# LQFP48_TO_DIP.net
KiCad netlist of a schematic drawn in EasyEDA
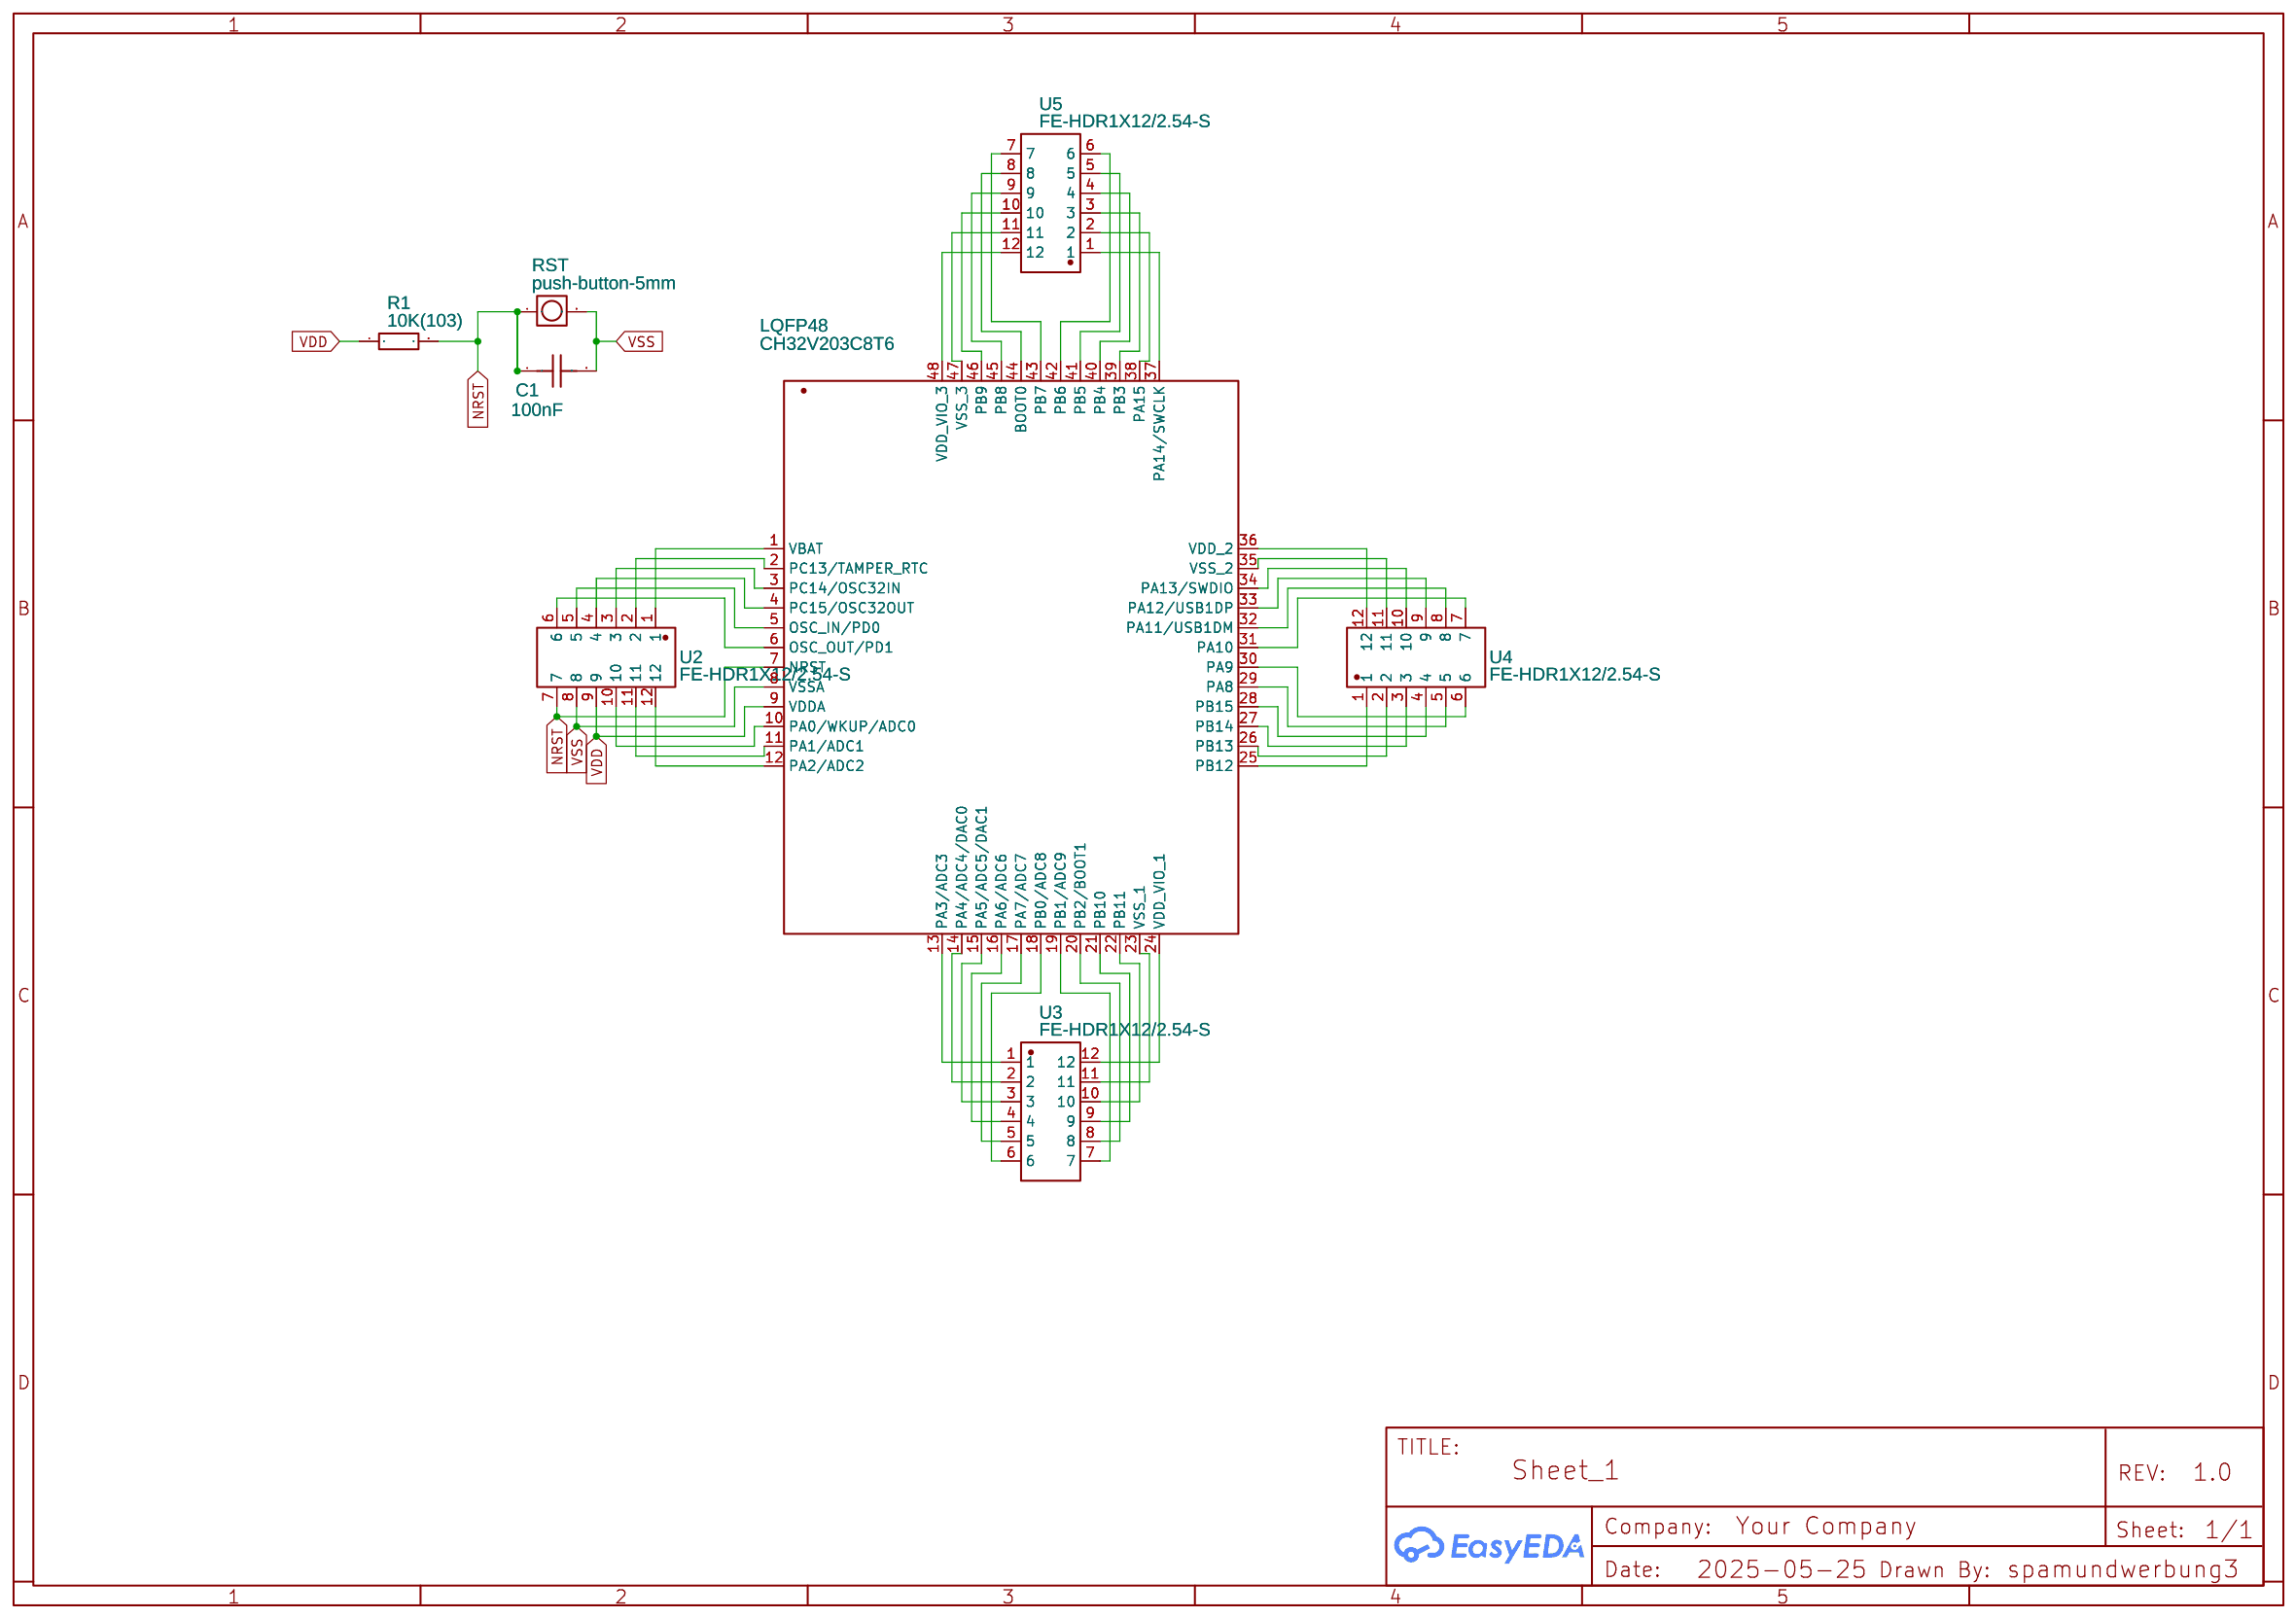
[diagram p0: schematic sheet]

(export (version "E")
  (design (tool "Eeschema 10.0.6"))
  (components
    (comp (ref "C1")
      (value "100nF")
      (fields (field (name "Manufacturer Part") "C0603B104K500NT") (field (name "Manufacturer") "TORCH(火炬)"))
      (libsource (lib "") (part "C100NF_0603"))
    )
    (comp (ref "LQFP48")
      (value "CH32V203C8T6")
      (fields (field (name "Manufacturer") "WCH(南京沁恒)"))
      (libsource (lib "") (part "CH32V203C8T6"))
    )
    (comp (ref "R1")
      (value "10K(103)")
      (fields (field (name "Manufacturer Part") "RC0603JR-0710KL") (field (name "Manufacturer") "YAGEO"))
      (libsource (lib "") (part "0603 10K RESISTOR (SMD)"))
    )
    (comp (ref "RST") (value "push-button-5mm") (libsource (lib "") (part "push-button-5mm")))
    (comp (ref "U2")
      (value "FE-HDR1X12/2.54-S")
      (fields (field (name "Manufacturer Part") "Fe-HDR1X12/2.54-S"))
      (libsource (lib "") (part "FE-HDR1X12/2.54-S_3"))
    )
    (comp (ref "U3")
      (value "FE-HDR1X12/2.54-S")
      (fields (field (name "Manufacturer Part") "Fe-HDR1X12/2.54-S"))
      (libsource (lib "") (part "FE-HDR1X12/2.54-S_2"))
    )
    (comp (ref "U4")
      (value "FE-HDR1X12/2.54-S")
      (fields (field (name "Manufacturer Part") "Fe-HDR1X12/2.54-S"))
      (libsource (lib "") (part "FE-HDR1X12/2.54-S"))
    )
    (comp (ref "U5")
      (value "FE-HDR1X12/2.54-S")
      (fields (field (name "Manufacturer Part") "Fe-HDR1X12/2.54-S"))
      (libsource (lib "") (part "FE-HDR1X12/2.54-S_1"))
    )
  )
  (nets
    (net (code "1") (name "NRST") (class "Default")
      (node (ref "C1") (pin "1") (pinfunction "1_1") (pintype "unspecified"))
      (node (ref "LQFP48") (pin "7") (pinfunction "NRST_7") (pintype "unspecified"))
      (node (ref "R1") (pin "2") (pinfunction "2_2") (pintype "input"))
      (node (ref "RST") (pin "1") (pinfunction "1_1") (pintype "unspecified"))
      (node (ref "U2") (pin "7") (pinfunction "7_7") (pintype "unspecified"))
    )
    (net (code "2") (name "Net-(LQFP48-BOOT0)") (class "Default")
      (node (ref "LQFP48") (pin "44") (pinfunction "BOOT0_44") (pintype "unspecified"))
      (node (ref "U5") (pin "8") (pinfunction "8_8") (pintype "unspecified"))
    )
    (net (code "3") (name "Net-(LQFP48-OSC_IN{slash}PD0)") (class "Default")
      (node (ref "LQFP48") (pin "5") (pinfunction "OSC_IN/PD0_5") (pintype "unspecified"))
      (node (ref "U2") (pin "5") (pinfunction "5_5") (pintype "unspecified"))
    )
    (net (code "4") (name "Net-(LQFP48-OSC_OUT{slash}PD1)") (class "Default")
      (node (ref "LQFP48") (pin "6") (pinfunction "OSC_OUT/PD1_6") (pintype "unspecified"))
      (node (ref "U2") (pin "6") (pinfunction "6_6") (pintype "unspecified"))
    )
    (net (code "5") (name "Net-(LQFP48-PA0{slash}WKUP{slash}ADC0)") (class "Default")
      (node (ref "LQFP48") (pin "10") (pinfunction "PA0/WKUP/ADC0_10") (pintype "unspecified"))
      (node (ref "U2") (pin "10") (pinfunction "10_10") (pintype "unspecified"))
    )
    (net (code "6") (name "Net-(LQFP48-PA1{slash}ADC1)") (class "Default")
      (node (ref "LQFP48") (pin "11") (pinfunction "PA1/ADC1_11") (pintype "unspecified"))
      (node (ref "U2") (pin "11") (pinfunction "11_11") (pintype "unspecified"))
    )
    (net (code "7") (name "Net-(LQFP48-PA2{slash}ADC2)") (class "Default")
      (node (ref "LQFP48") (pin "12") (pinfunction "PA2/ADC2_12") (pintype "unspecified"))
      (node (ref "U2") (pin "12") (pinfunction "12_12") (pintype "unspecified"))
    )
    (net (code "8") (name "Net-(LQFP48-PA3{slash}ADC3)") (class "Default")
      (node (ref "LQFP48") (pin "13") (pinfunction "PA3/ADC3_13") (pintype "unspecified"))
      (node (ref "U3") (pin "1") (pinfunction "1_1") (pintype "unspecified"))
    )
    (net (code "9") (name "Net-(LQFP48-PA4{slash}ADC4{slash}DAC0)") (class "Default")
      (node (ref "LQFP48") (pin "14") (pinfunction "PA4/ADC4/DAC0_14") (pintype "unspecified"))
      (node (ref "U3") (pin "2") (pinfunction "2_2") (pintype "unspecified"))
    )
    (net (code "10") (name "Net-(LQFP48-PA5{slash}ADC5{slash}DAC1)") (class "Default")
      (node (ref "LQFP48") (pin "15") (pinfunction "PA5/ADC5/DAC1_15") (pintype "unspecified"))
      (node (ref "U3") (pin "3") (pinfunction "3_3") (pintype "unspecified"))
    )
    (net (code "11") (name "Net-(LQFP48-PA6{slash}ADC6)") (class "Default")
      (node (ref "LQFP48") (pin "16") (pinfunction "PA6/ADC6_16") (pintype "unspecified"))
      (node (ref "U3") (pin "4") (pinfunction "4_4") (pintype "unspecified"))
    )
    (net (code "12") (name "Net-(LQFP48-PA7{slash}ADC7)") (class "Default")
      (node (ref "LQFP48") (pin "17") (pinfunction "PA7/ADC7_17") (pintype "unspecified"))
      (node (ref "U3") (pin "5") (pinfunction "5_5") (pintype "unspecified"))
    )
    (net (code "13") (name "Net-(LQFP48-PA8)") (class "Default")
      (node (ref "LQFP48") (pin "29") (pinfunction "PA8_29") (pintype "unspecified"))
      (node (ref "U4") (pin "5") (pinfunction "5_5") (pintype "unspecified"))
    )
    (net (code "14") (name "Net-(LQFP48-PA9)") (class "Default")
      (node (ref "LQFP48") (pin "30") (pinfunction "PA9_30") (pintype "unspecified"))
      (node (ref "U4") (pin "6") (pinfunction "6_6") (pintype "unspecified"))
    )
    (net (code "15") (name "Net-(LQFP48-PA10)") (class "Default")
      (node (ref "LQFP48") (pin "31") (pinfunction "PA10_31") (pintype "unspecified"))
      (node (ref "U4") (pin "7") (pinfunction "7_7") (pintype "unspecified"))
    )
    (net (code "16") (name "Net-(LQFP48-PA11{slash}USB1DM)") (class "Default")
      (node (ref "LQFP48") (pin "32") (pinfunction "PA11/USB1DM_32") (pintype "unspecified"))
      (node (ref "U4") (pin "8") (pinfunction "8_8") (pintype "unspecified"))
    )
    (net (code "17") (name "Net-(LQFP48-PA12{slash}USB1DP)") (class "Default")
      (node (ref "LQFP48") (pin "33") (pinfunction "PA12/USB1DP_33") (pintype "unspecified"))
      (node (ref "U4") (pin "9") (pinfunction "9_9") (pintype "unspecified"))
    )
    (net (code "18") (name "Net-(LQFP48-PA13{slash}SWDIO)") (class "Default")
      (node (ref "LQFP48") (pin "34") (pinfunction "PA13/SWDIO_34") (pintype "unspecified"))
      (node (ref "U4") (pin "10") (pinfunction "10_10") (pintype "unspecified"))
    )
    (net (code "19") (name "Net-(LQFP48-PA14{slash}SWCLK)") (class "Default")
      (node (ref "LQFP48") (pin "37") (pinfunction "PA14/SWCLK_37") (pintype "unspecified"))
      (node (ref "U5") (pin "1") (pinfunction "1_1") (pintype "unspecified"))
    )
    (net (code "20") (name "Net-(LQFP48-PA15)") (class "Default")
      (node (ref "LQFP48") (pin "38") (pinfunction "PA15_38") (pintype "unspecified"))
      (node (ref "U5") (pin "2") (pinfunction "2_2") (pintype "unspecified"))
    )
    (net (code "21") (name "Net-(LQFP48-PB0{slash}ADC8)") (class "Default")
      (node (ref "LQFP48") (pin "18") (pinfunction "PB0/ADC8_18") (pintype "unspecified"))
      (node (ref "U3") (pin "6") (pinfunction "6_6") (pintype "unspecified"))
    )
    (net (code "22") (name "Net-(LQFP48-PB1{slash}ADC9)") (class "Default")
      (node (ref "LQFP48") (pin "19") (pinfunction "PB1/ADC9_19") (pintype "unspecified"))
      (node (ref "U3") (pin "7") (pinfunction "7_7") (pintype "unspecified"))
    )
    (net (code "23") (name "Net-(LQFP48-PB2{slash}BOOT1)") (class "Default")
      (node (ref "LQFP48") (pin "20") (pinfunction "PB2/BOOT1_20") (pintype "unspecified"))
      (node (ref "U3") (pin "8") (pinfunction "8_8") (pintype "unspecified"))
    )
    (net (code "24") (name "Net-(LQFP48-PB3)") (class "Default")
      (node (ref "LQFP48") (pin "39") (pinfunction "PB3_39") (pintype "unspecified"))
      (node (ref "U5") (pin "3") (pinfunction "3_3") (pintype "unspecified"))
    )
    (net (code "25") (name "Net-(LQFP48-PB4)") (class "Default")
      (node (ref "LQFP48") (pin "40") (pinfunction "PB4_40") (pintype "unspecified"))
      (node (ref "U5") (pin "4") (pinfunction "4_4") (pintype "unspecified"))
    )
    (net (code "26") (name "Net-(LQFP48-PB5)") (class "Default")
      (node (ref "LQFP48") (pin "41") (pinfunction "PB5_41") (pintype "unspecified"))
      (node (ref "U5") (pin "5") (pinfunction "5_5") (pintype "unspecified"))
    )
    (net (code "27") (name "Net-(LQFP48-PB6)") (class "Default")
      (node (ref "LQFP48") (pin "42") (pinfunction "PB6_42") (pintype "unspecified"))
      (node (ref "U5") (pin "6") (pinfunction "6_6") (pintype "unspecified"))
    )
    (net (code "28") (name "Net-(LQFP48-PB7)") (class "Default")
      (node (ref "LQFP48") (pin "43") (pinfunction "PB7_43") (pintype "unspecified"))
      (node (ref "U5") (pin "7") (pinfunction "7_7") (pintype "unspecified"))
    )
    (net (code "29") (name "Net-(LQFP48-PB8)") (class "Default")
      (node (ref "LQFP48") (pin "45") (pinfunction "PB8_45") (pintype "unspecified"))
      (node (ref "U5") (pin "9") (pinfunction "9_9") (pintype "unspecified"))
    )
    (net (code "30") (name "Net-(LQFP48-PB9)") (class "Default")
      (node (ref "LQFP48") (pin "46") (pinfunction "PB9_46") (pintype "unspecified"))
      (node (ref "U5") (pin "10") (pinfunction "10_10") (pintype "unspecified"))
    )
    (net (code "31") (name "Net-(LQFP48-PB10)") (class "Default")
      (node (ref "LQFP48") (pin "21") (pinfunction "PB10_21") (pintype "unspecified"))
      (node (ref "U3") (pin "9") (pinfunction "9_9") (pintype "unspecified"))
    )
    (net (code "32") (name "Net-(LQFP48-PB11)") (class "Default")
      (node (ref "LQFP48") (pin "22") (pinfunction "PB11_22") (pintype "unspecified"))
      (node (ref "U3") (pin "10") (pinfunction "10_10") (pintype "unspecified"))
    )
    (net (code "33") (name "Net-(LQFP48-PB12)") (class "Default")
      (node (ref "LQFP48") (pin "25") (pinfunction "PB12_25") (pintype "unspecified"))
      (node (ref "U4") (pin "1") (pinfunction "1_1") (pintype "unspecified"))
    )
    (net (code "34") (name "Net-(LQFP48-PB13)") (class "Default")
      (node (ref "LQFP48") (pin "26") (pinfunction "PB13_26") (pintype "unspecified"))
      (node (ref "U4") (pin "2") (pinfunction "2_2") (pintype "unspecified"))
    )
    (net (code "35") (name "Net-(LQFP48-PB14)") (class "Default")
      (node (ref "LQFP48") (pin "27") (pinfunction "PB14_27") (pintype "unspecified"))
      (node (ref "U4") (pin "3") (pinfunction "3_3") (pintype "unspecified"))
    )
    (net (code "36") (name "Net-(LQFP48-PB15)") (class "Default")
      (node (ref "LQFP48") (pin "28") (pinfunction "PB15_28") (pintype "unspecified"))
      (node (ref "U4") (pin "4") (pinfunction "4_4") (pintype "unspecified"))
    )
    (net (code "37") (name "Net-(LQFP48-PC13{slash}TAMPER_RTC)") (class "Default")
      (node (ref "LQFP48") (pin "2") (pinfunction "PC13/TAMPER_RTC_2") (pintype "unspecified"))
      (node (ref "U2") (pin "2") (pinfunction "2_2") (pintype "unspecified"))
    )
    (net (code "38") (name "Net-(LQFP48-PC14{slash}OSC32IN)") (class "Default")
      (node (ref "LQFP48") (pin "3") (pinfunction "PC14/OSC32IN_3") (pintype "unspecified"))
      (node (ref "U2") (pin "3") (pinfunction "3_3") (pintype "unspecified"))
    )
    (net (code "39") (name "Net-(LQFP48-PC15{slash}OSC32OUT)") (class "Default")
      (node (ref "LQFP48") (pin "4") (pinfunction "PC15/OSC32OUT_4") (pintype "unspecified"))
      (node (ref "U2") (pin "4") (pinfunction "4_4") (pintype "unspecified"))
    )
    (net (code "40") (name "Net-(LQFP48-VBAT)") (class "Default")
      (node (ref "LQFP48") (pin "1") (pinfunction "VBAT_1") (pintype "unspecified"))
      (node (ref "U2") (pin "1") (pinfunction "1_1") (pintype "unspecified"))
    )
    (net (code "41") (name "Net-(LQFP48-VDD_2)") (class "Default")
      (node (ref "LQFP48") (pin "36") (pinfunction "VDD_2_36") (pintype "unspecified"))
      (node (ref "U4") (pin "12") (pinfunction "12_12") (pintype "unspecified"))
    )
    (net (code "42") (name "Net-(LQFP48-VDD_VIO_1)") (class "Default")
      (node (ref "LQFP48") (pin "24") (pinfunction "VDD_VIO_1_24") (pintype "unspecified"))
      (node (ref "U3") (pin "12") (pinfunction "12_12") (pintype "unspecified"))
    )
    (net (code "43") (name "Net-(LQFP48-VDD_VIO_3)") (class "Default")
      (node (ref "LQFP48") (pin "48") (pinfunction "VDD_VIO_3_48") (pintype "unspecified"))
      (node (ref "U5") (pin "12") (pinfunction "12_12") (pintype "unspecified"))
    )
    (net (code "44") (name "Net-(LQFP48-VSS_1)") (class "Default")
      (node (ref "LQFP48") (pin "23") (pinfunction "VSS_1_23") (pintype "unspecified"))
      (node (ref "U3") (pin "11") (pinfunction "11_11") (pintype "unspecified"))
    )
    (net (code "45") (name "Net-(LQFP48-VSS_2)") (class "Default")
      (node (ref "LQFP48") (pin "35") (pinfunction "VSS_2_35") (pintype "unspecified"))
      (node (ref "U4") (pin "11") (pinfunction "11_11") (pintype "unspecified"))
    )
    (net (code "46") (name "Net-(LQFP48-VSS_3)") (class "Default")
      (node (ref "LQFP48") (pin "47") (pinfunction "VSS_3_47") (pintype "unspecified"))
      (node (ref "U5") (pin "11") (pinfunction "11_11") (pintype "unspecified"))
    )
    (net (code "47") (name "VDD") (class "Default")
      (node (ref "LQFP48") (pin "9") (pinfunction "VDDA_9") (pintype "unspecified"))
      (node (ref "R1") (pin "1") (pinfunction "1_1") (pintype "input"))
      (node (ref "U2") (pin "9") (pinfunction "9_9") (pintype "unspecified"))
    )
    (net (code "48") (name "VSS") (class "Default")
      (node (ref "C1") (pin "2") (pinfunction "2_2") (pintype "unspecified"))
      (node (ref "LQFP48") (pin "8") (pinfunction "VSSA_8") (pintype "unspecified"))
      (node (ref "RST") (pin "2") (pinfunction "2_2") (pintype "unspecified"))
      (node (ref "U2") (pin "8") (pinfunction "8_8") (pintype "unspecified"))
    )
  )
)
